# H_Bridge.net
KiCad netlist of a schematic drawn in Altium Designer
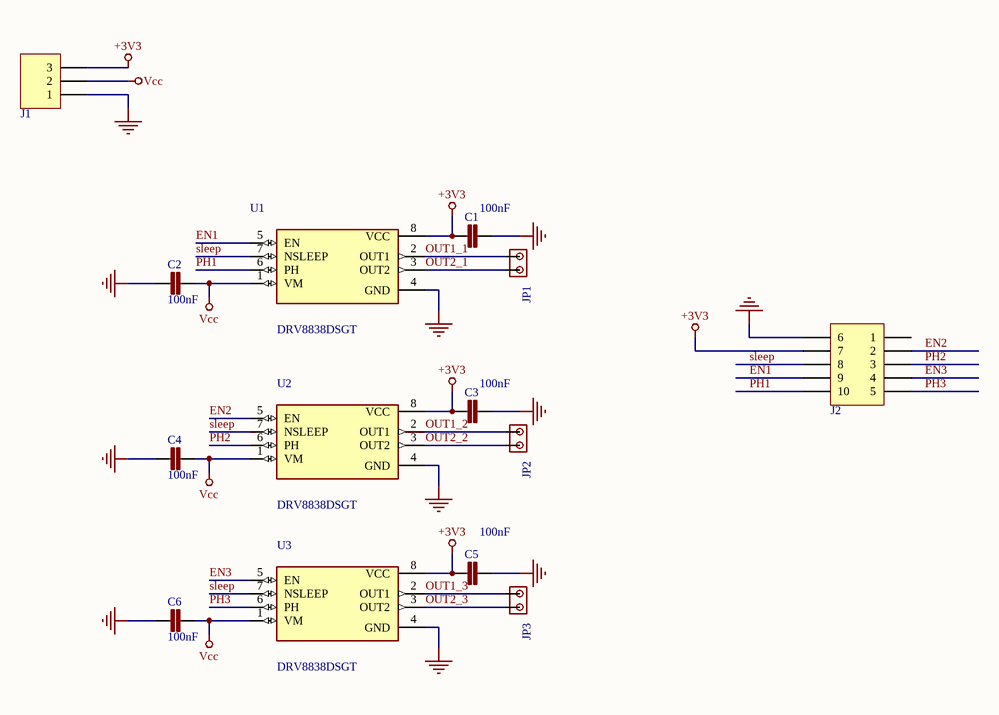
[diagram p0: H_Bridge.SchDoc]

(export (version "E")
  (design (tool "Eeschema 10.0.6"))
  (components
    (comp (ref "C1")
      (value "100nF")
      (footprint "C0603")
      (fields (field (name "PART NUMBER") "06033C104KAT2A") (field (name "Comment") "C-EUC0603"))
      (libsource (lib "rcl") (part "C-EUC0603"))
    )
    (comp (ref "C2")
      (value "100nF")
      (footprint "C0603")
      (fields (field (name "PART NUMBER") "06033C104KAT2A") (field (name "Comment") "C-EUC0603"))
      (libsource (lib "") (part "C-EUC0603_1"))
    )
    (comp (ref "C3")
      (value "100nF")
      (footprint "C0603")
      (fields (field (name "PART NUMBER") "06033C104KAT2A") (field (name "Comment") "C-EUC0603"))
      (libsource (lib "rcl") (part "C-EUC0603"))
    )
    (comp (ref "C4")
      (value "100nF")
      (footprint "C0603")
      (fields (field (name "PART NUMBER") "06033C104KAT2A") (field (name "Comment") "C-EUC0603"))
      (libsource (lib "") (part "C-EUC0603_1"))
    )
    (comp (ref "C5")
      (value "100nF")
      (footprint "C0603")
      (fields (field (name "PART NUMBER") "06033C104KAT2A") (field (name "Comment") "C-EUC0603"))
      (libsource (lib "rcl") (part "C-EUC0603"))
    )
    (comp (ref "C6")
      (value "100nF")
      (footprint "C0603")
      (fields (field (name "PART NUMBER") "06033C104KAT2A") (field (name "Comment") "C-EUC0603"))
      (libsource (lib "") (part "C-EUC0603_1"))
    )
    (comp (ref "J1")
      (value "03p")
      (footprint "61300311121")
      (description "WR-PHD 2.54 mm THT Pin Header, 03p")
      (fields (field (name "PART NUMBER") "61300311121"))
      (libsource (lib "Male_header_254mm") (part "61300311121"))
    )
    (comp (ref "J2")
      (value "10p")
      (footprint "61301021121")
      (description "WR-PHD 2.54 mm THT Dual Pin Header, 10p")
      (fields (field (name "PART NUMBER") "61301021121"))
      (libsource (lib "Male_header_254mm") (part "61301021121"))
    )
    (comp (ref "JP1")
      (value "CONECT_BAT")
      (footprint "CONECT_BAT_PCK")
      (libsource (lib "TE") (part "CONECT_BAT"))
    )
    (comp (ref "JP2")
      (value "CONECT_BAT")
      (footprint "CONECT_BAT_PCK")
      (libsource (lib "TE") (part "CONECT_BAT"))
    )
    (comp (ref "JP3")
      (value "CONECT_BAT")
      (footprint "CONECT_BAT_PCK")
      (libsource (lib "TE") (part "CONECT_BAT"))
    )
    (comp (ref "U1")
      (value "DRV8838DSGT")
      (footprint "SON50P200X200X80-9N")
      (description "1.8A Low Voltage Brushed DC Motor Driver 8-WSON -40 to 85")
      (fields (field (name "MF") "Texas Instruments"))
      (libsource (lib "texas") (part "DRV8838DSGT"))
    )
    (comp (ref "U2")
      (value "DRV8838DSGT")
      (footprint "SON50P200X200X80-9N")
      (description "1.8A Low Voltage Brushed DC Motor Driver 8-WSON -40 to 85")
      (fields (field (name "MF") "Texas Instruments"))
      (libsource (lib "texas") (part "DRV8838DSGT"))
    )
    (comp (ref "U3")
      (value "DRV8838DSGT")
      (footprint "SON50P200X200X80-9N")
      (description "1.8A Low Voltage Brushed DC Motor Driver 8-WSON -40 to 85")
      (fields (field (name "MF") "Texas Instruments"))
      (libsource (lib "texas") (part "DRV8838DSGT"))
    )
  )
  (nets
    (net (code "1") (name "+3V3") (class "Default")
      (node (ref "C1") (pin "1") (pinfunction "1_1") (pintype "passive"))
      (node (ref "C3") (pin "1") (pinfunction "1_1") (pintype "passive"))
      (node (ref "C5") (pin "1") (pinfunction "1_1") (pintype "passive"))
      (node (ref "J1") (pin "3") (pinfunction "3_3") (pintype "passive"))
      (node (ref "J2") (pin "7") (pinfunction "7_7") (pintype "passive"))
      (node (ref "U1") (pin "8") (pinfunction "VCC_8") (pintype "power_in"))
      (node (ref "U2") (pin "8") (pinfunction "VCC_8") (pintype "power_in"))
      (node (ref "U3") (pin "8") (pinfunction "VCC_8") (pintype "power_in"))
    )
    (net (code "2") (name "/EN1") (class "Default")
      (node (ref "J2") (pin "9") (pinfunction "9_9") (pintype "passive"))
      (node (ref "U1") (pin "5") (pinfunction "EN_5") (pintype "bidirectional"))
    )
    (net (code "3") (name "/EN2") (class "Default")
      (node (ref "J2") (pin "2") (pinfunction "2_2") (pintype "passive"))
      (node (ref "U2") (pin "5") (pinfunction "EN_5") (pintype "bidirectional"))
    )
    (net (code "4") (name "/EN3") (class "Default")
      (node (ref "J2") (pin "4") (pinfunction "4_4") (pintype "passive"))
      (node (ref "U3") (pin "5") (pinfunction "EN_5") (pintype "bidirectional"))
    )
    (net (code "5") (name "/OUT1_1") (class "Default")
      (node (ref "JP1") (pin "1") (pinfunction "1_1") (pintype "passive"))
      (node (ref "U1") (pin "2") (pinfunction "OUT1_2") (pintype "output"))
    )
    (net (code "6") (name "/OUT1_2") (class "Default")
      (node (ref "JP2") (pin "1") (pinfunction "1_1") (pintype "passive"))
      (node (ref "U2") (pin "2") (pinfunction "OUT1_2") (pintype "output"))
    )
    (net (code "7") (name "/OUT1_3") (class "Default")
      (node (ref "JP3") (pin "1") (pinfunction "1_1") (pintype "passive"))
      (node (ref "U3") (pin "2") (pinfunction "OUT1_2") (pintype "output"))
    )
    (net (code "8") (name "/OUT2_1") (class "Default")
      (node (ref "JP1") (pin "2") (pinfunction "2_2") (pintype "passive"))
      (node (ref "U1") (pin "3") (pinfunction "OUT2_3") (pintype "output"))
    )
    (net (code "9") (name "/OUT2_2") (class "Default")
      (node (ref "JP2") (pin "2") (pinfunction "2_2") (pintype "passive"))
      (node (ref "U2") (pin "3") (pinfunction "OUT2_3") (pintype "output"))
    )
    (net (code "10") (name "/OUT2_3") (class "Default")
      (node (ref "JP3") (pin "2") (pinfunction "2_2") (pintype "passive"))
      (node (ref "U3") (pin "3") (pinfunction "OUT2_3") (pintype "output"))
    )
    (net (code "11") (name "/PH1") (class "Default")
      (node (ref "J2") (pin "10") (pinfunction "10_10") (pintype "passive"))
      (node (ref "U1") (pin "6") (pinfunction "PH_6") (pintype "bidirectional"))
    )
    (net (code "12") (name "/PH2") (class "Default")
      (node (ref "J2") (pin "3") (pinfunction "3_3") (pintype "passive"))
      (node (ref "U2") (pin "6") (pinfunction "PH_6") (pintype "bidirectional"))
    )
    (net (code "13") (name "/PH3") (class "Default")
      (node (ref "J2") (pin "5") (pinfunction "5_5") (pintype "passive"))
      (node (ref "U3") (pin "6") (pinfunction "PH_6") (pintype "bidirectional"))
    )
    (net (code "14") (name "/sleep") (class "Default")
      (node (ref "J2") (pin "8") (pinfunction "8_8") (pintype "passive"))
      (node (ref "U1") (pin "7") (pinfunction "NSLEEP_7") (pintype "bidirectional"))
      (node (ref "U2") (pin "7") (pinfunction "NSLEEP_7") (pintype "bidirectional"))
      (node (ref "U3") (pin "7") (pinfunction "NSLEEP_7") (pintype "bidirectional"))
    )
    (net (code "15") (name "GND") (class "Default")
      (node (ref "C1") (pin "2") (pinfunction "2_2") (pintype "passive"))
      (node (ref "C2") (pin "2") (pinfunction "2_2") (pintype "passive"))
      (node (ref "C3") (pin "2") (pinfunction "2_2") (pintype "passive"))
      (node (ref "C4") (pin "2") (pinfunction "2_2") (pintype "passive"))
      (node (ref "C5") (pin "2") (pinfunction "2_2") (pintype "passive"))
      (node (ref "C6") (pin "2") (pinfunction "2_2") (pintype "passive"))
      (node (ref "J1") (pin "1") (pinfunction "1_1") (pintype "passive"))
      (node (ref "J2") (pin "6") (pinfunction "6_6") (pintype "passive"))
      (node (ref "U1") (pin "4") (pinfunction "GND_4") (pintype "power_in"))
      (node (ref "U2") (pin "4") (pinfunction "GND_4") (pintype "power_in"))
      (node (ref "U3") (pin "4") (pinfunction "GND_4") (pintype "power_in"))
    )
    (net (code "16") (name "Vcc") (class "Default")
      (node (ref "C2") (pin "1") (pinfunction "1_1") (pintype "passive"))
      (node (ref "C4") (pin "1") (pinfunction "1_1") (pintype "passive"))
      (node (ref "C6") (pin "1") (pinfunction "1_1") (pintype "passive"))
      (node (ref "J1") (pin "2") (pinfunction "2_2") (pintype "passive"))
      (node (ref "U1") (pin "1") (pinfunction "VM_1") (pintype "bidirectional"))
      (node (ref "U2") (pin "1") (pinfunction "VM_1") (pintype "bidirectional"))
      (node (ref "U3") (pin "1") (pinfunction "VM_1") (pintype "bidirectional"))
    )
    (net (code "17") (name "unconnected-(J2-Pad1)") (class "Default")
      (node (ref "J2") (pin "1") (pinfunction "1_1") (pintype "passive"))
    )
  )
)
